# DC_Buck_Converter_5V_-_After.net
KiCad netlist of a schematic drawn in Altium Designer
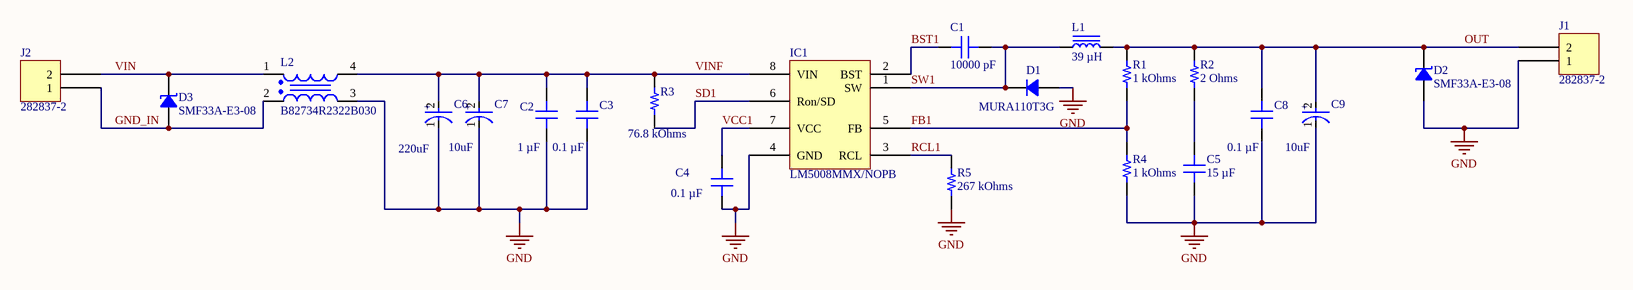
[diagram p0: DC_Buck_Converter_5V - After.SchDoc]

(export (version "E")
  (design (tool "Eeschema 10.0.6"))
  (components
    (comp (ref "C1")
      (value "10000 pF")
      (footprint "CAP 0603_1608")
      (description "CAP CER 10000PF 100V X7R 0603")
      (fields (field (name "PART NUMBER") "AC0603KRX7R0BB103") (field (name "MANUFACTURER") "Yageo"))
      (libsource (lib "Celestial Altium Library - altium_library") (part "Capacitor"))
    )
    (comp (ref "C2")
      (value "1 µF")
      (footprint "CAP 0603_1608")
      (description "CAP CER 1UF 50V X5R 0603")
      (fields (field (name "PART NUMBER") "UMK107ABJ105MAHT") (field (name "MANUFACTURER") "Taiyo Yuden"))
      (libsource (lib "Celestial Altium Library - altium_library") (part "Capacitor"))
    )
    (comp (ref "C3")
      (value "0.1 µF")
      (footprint "CAP 0603_1608")
      (description "CAP CER 0.1UF 50V X7R 0603")
      (fields (field (name "PART NUMBER") "C0603C104K5RAC7411") (field (name "MANUFACTURER") "KEMET"))
      (libsource (lib "Celestial Altium Library - altium_library") (part "Capacitor"))
    )
    (comp (ref "C4")
      (value "0.1 µF")
      (footprint "CAP 0603_1608")
      (description "CAP CER 0.1UF 50V X7R 0603")
      (fields (field (name "PART NUMBER") "C0603C104K5RAC7411") (field (name "MANUFACTURER") "KEMET"))
      (libsource (lib "Celestial Altium Library - altium_library") (part "Capacitor"))
    )
    (comp (ref "C5")
      (value "15 µF")
      (footprint "CAP 0603_1608")
      (description "CAP CER 15UF 6.3V X5R 0603")
      (fields
        (field (name "PART NUMBER") "C1608X5R0J156M080AC")
        (field (name "MANUFACTURER") "TDK Corporation")
      )
      (libsource (lib "Celestial Altium Library - altium_library") (part "Capacitor"))
    )
    (comp (ref "C6")
      (value "EEE-FC1H221P")
      (footprint "FP-FC-G-MFG")
      (description "CAP ALUM 220UF 20% 50V SMD")
      (fields
        (field (name "VOLTAGE") "50V")
        (field (name "TOLERANCE") "20%")
        (field (name "CAPACITANCE") "220uF")
      )
      (libsource (lib "Altium Content Vault") (part "203bc49f2ac43e59fd269a8c329ed05"))
    )
    (comp (ref "C7")
      (value "UUT1H100MCL1GS")
      (footprint "FP-UUT1H100MCL1GS-MFG")
      (description "CAP ALUM 10UF 20% 50V SMD")
      (fields
        (field (name "CAPACITANCE") "10uF")
        (field (name "VOLTAGE") "50V")
        (field (name "TOLERANCE") "20%")
      )
      (libsource (lib "Altium Content Vault") (part "cf48714ba7e38822c1575c7ec0b6d1f"))
    )
    (comp (ref "C8")
      (value "0.1 µF")
      (footprint "CAP 0603_1608")
      (description "CAP CER 0.1UF 50V X7R 0603")
      (fields (field (name "PART NUMBER") "C0603C104K5RAC7411") (field (name "MANUFACTURER") "KEMET"))
      (libsource (lib "Celestial Altium Library - altium_library") (part "Capacitor"))
    )
    (comp (ref "C9")
      (value "UUT1H100MCL1GS")
      (footprint "FP-UUT1H100MCL1GS-MFG")
      (description "CAP ALUM 10UF 20% 50V SMD")
      (fields
        (field (name "CAPACITANCE") "10uF")
        (field (name "VOLTAGE") "50V")
        (field (name "TOLERANCE") "20%")
      )
      (libsource (lib "Altium Content Vault") (part "cf48714ba7e38822c1575c7ec0b6d1f"))
    )
    (comp (ref "D1")
      (value "MURA110T3G")
      (footprint "DO214AC SMA")
      (description "DIODE GEN PURP 100V 2A SMA")
      (fields (field (name "MANUFACTURER") "ON Semiconductor"))
      (libsource (lib "Celestial Altium Library - altium_library") (part "Diode"))
    )
    (comp (ref "D2")
      (value "SMF33A-E3-08")
      (footprint "SMF DO-219AB")
      (description "TVS DIODE 33V 53.3V SMF")
      (fields (field (name "MANUFACTURER") "Vishay Semiconductor Diodes Division"))
      (libsource (lib "Celestial Altium Library - altium_library") (part "DIODE TVS UNI"))
    )
    (comp (ref "D3")
      (value "SMF33A-E3-08")
      (footprint "SMF DO-219AB")
      (description "TVS DIODE 33V 53.3V SMF")
      (fields (field (name "MANUFACTURER") "Vishay Semiconductor Diodes Division"))
      (libsource (lib "Celestial Altium Library - altium_library") (part "DIODE TVS UNI"))
    )
    (comp (ref "IC1")
      (value "LM5008MMX/NOPB")
      (footprint "TI VSSOP-8 DGK")
      (description "IC REG BUCK ADJ 350MA 8VSSOP")
      (fields (field (name "MANUFACTURER") "Texas Instruments"))
      (libsource (lib "Celestial Altium Library - altium_library") (part "TI LM5008"))
    )
    (comp (ref "J1")
      (value "282837-2")
      (footprint "TE 282837-2")
      (description "TERM BLK 2P SIDE ENT 5.08MM PCB")
      (fields (field (name "MANUFACTURER") "TE Connectivity AMP Connectors") (field (name "VOLTAGE") "300 V"))
      (libsource (lib "DC_Buck_Converter_5V") (part "282837-2"))
    )
    (comp (ref "J2")
      (value "282837-2")
      (footprint "TE 282837-2")
      (description "TERM BLK 2P SIDE ENT 5.08MM PCB")
      (fields (field (name "MANUFACTURER") "TE Connectivity AMP Connectors") (field (name "VOLTAGE") "300 V"))
      (libsource (lib "") (part "282837-2_1"))
    )
    (comp (ref "L1")
      (value "39 µH")
      (footprint "BOURNS SRR1280")
      (description "FIXED IND 39UH 3.2A 70 MOHM SMD")
      (fields (field (name "PART NUMBER") "SRR1280-390M") (field (name "MANUFACTURER") "Bourns Inc."))
      (libsource (lib "Celestial Altium Library - altium_library") (part "Inductor"))
    )
    (comp (ref "L2")
      (value "Choke Alt")
      (footprint "B82732R2112B30")
      (fields (field (name "PART NUMBER") "B82734R2322B030") (field (name "MANUFACTURER") "TDK"))
      (libsource (lib "Passives_Inductor_THT") (part "Choke Alt"))
    )
    (comp (ref "R1")
      (value "1 kOhms")
      (footprint "RES 0603_1608")
      (description "RES SMD 1K OHM 0.5% 1/10W 0603")
      (fields (field (name "PART NUMBER") "AT0603DRD071KL") (field (name "MANUFACTURER") "Yageo"))
      (libsource (lib "Celestial Altium Library - altium_library") (part "Resistor"))
    )
    (comp (ref "R2")
      (value "2 Ohms")
      (footprint "RES 0603_1608")
      (description "SULFUR TOLERANT CHIP RESISTORS")
      (fields (field (name "PART NUMBER") "SFR03EZPJ2R0") (field (name "MANUFACTURER") "Rohm Semiconductor"))
      (libsource (lib "Celestial Altium Library - altium_library") (part "Resistor"))
    )
    (comp (ref "R3")
      (value "76.8 kOhms")
      (footprint "RES 0603_1608")
      (description "RES SMD 76.8KOHM 0.1% 1/10W 0603")
      (fields (field (name "PART NUMBER") "RG1608P-7682-B-T5") (field (name "MANUFACTURER") "Susumu"))
      (libsource (lib "Celestial Altium Library - altium_library") (part "Resistor"))
    )
    (comp (ref "R4")
      (value "1 kOhms")
      (footprint "RES 0603_1608")
      (description "RES SMD 1K OHM 0.5% 1/10W 0603")
      (fields (field (name "PART NUMBER") "AT0603DRD071KL") (field (name "MANUFACTURER") "Yageo"))
      (libsource (lib "Celestial Altium Library - altium_library") (part "Resistor"))
    )
    (comp (ref "R5")
      (value "267 kOhms")
      (footprint "RES 0603_1608")
      (description "RES SMD 267K OHM 0.1% 1/10W 0603")
      (fields (field (name "PART NUMBER") "RT0603BRD07267KL") (field (name "MANUFACTURER") "Yageo"))
      (libsource (lib "Celestial Altium Library - altium_library") (part "Resistor"))
    )
  )
  (nets
    (net (code "1") (name "/BST1") (class "Default")
      (node (ref "C1") (pin "1") (pinfunction "1_1") (pintype "passive"))
      (node (ref "IC1") (pin "2") (pinfunction "BST_2") (pintype "passive"))
    )
    (net (code "2") (name "/FB1") (class "Default")
      (node (ref "IC1") (pin "5") (pinfunction "FB_5") (pintype "passive"))
      (node (ref "R1") (pin "1") (pinfunction "1_1") (pintype "passive"))
      (node (ref "R4") (pin "2") (pinfunction "2_2") (pintype "passive"))
    )
    (net (code "3") (name "/GND_IN") (class "Default")
      (node (ref "D3") (pin "1") (pinfunction "1_1") (pintype "passive"))
      (node (ref "J2") (pin "1") (pinfunction "1_1") (pintype "passive"))
      (node (ref "L2") (pin "2") (pinfunction "2_2") (pintype "passive"))
    )
    (net (code "4") (name "/OUT") (class "Default")
      (node (ref "C8") (pin "2") (pinfunction "2_2") (pintype "passive"))
      (node (ref "C9") (pin "2") (pinfunction "A_2") (pintype "passive"))
      (node (ref "D2") (pin "2") (pinfunction "2_2") (pintype "passive"))
      (node (ref "J1") (pin "2") (pinfunction "2_2") (pintype "passive"))
      (node (ref "L1") (pin "2") (pinfunction "2_2") (pintype "passive"))
      (node (ref "R1") (pin "2") (pinfunction "2_2") (pintype "passive"))
      (node (ref "R2") (pin "2") (pinfunction "2_2") (pintype "passive"))
    )
    (net (code "5") (name "/RCL1") (class "Default")
      (node (ref "IC1") (pin "3") (pinfunction "RCL_3") (pintype "passive"))
      (node (ref "R5") (pin "2") (pinfunction "2_2") (pintype "passive"))
    )
    (net (code "6") (name "/SD1") (class "Default")
      (node (ref "IC1") (pin "6") (pinfunction "Ron/SD_6") (pintype "passive"))
      (node (ref "R3") (pin "1") (pinfunction "1_1") (pintype "passive"))
    )
    (net (code "7") (name "/SW1") (class "Default")
      (node (ref "C1") (pin "2") (pinfunction "2_2") (pintype "passive"))
      (node (ref "D1") (pin "2") (pinfunction "2_2") (pintype "passive"))
      (node (ref "IC1") (pin "1") (pinfunction "SW_1") (pintype "passive"))
      (node (ref "L1") (pin "1") (pinfunction "1_1") (pintype "passive"))
    )
    (net (code "8") (name "/VCC1") (class "Default")
      (node (ref "C4") (pin "1") (pinfunction "1_1") (pintype "passive"))
      (node (ref "IC1") (pin "7") (pinfunction "VCC_7") (pintype "passive"))
    )
    (net (code "9") (name "/VIN") (class "Default")
      (node (ref "D3") (pin "2") (pinfunction "2_2") (pintype "passive"))
      (node (ref "J2") (pin "2") (pinfunction "2_2") (pintype "passive"))
      (node (ref "L2") (pin "1") (pinfunction "1_1") (pintype "passive"))
    )
    (net (code "10") (name "/VINF") (class "Default")
      (node (ref "C2") (pin "2") (pinfunction "2_2") (pintype "passive"))
      (node (ref "C3") (pin "2") (pinfunction "2_2") (pintype "passive"))
      (node (ref "C6") (pin "2") (pinfunction "A_2") (pintype "passive"))
      (node (ref "C7") (pin "2") (pinfunction "A_2") (pintype "passive"))
      (node (ref "IC1") (pin "8") (pinfunction "VIN_8") (pintype "passive"))
      (node (ref "L2") (pin "4") (pinfunction "4_4") (pintype "passive"))
      (node (ref "R3") (pin "2") (pinfunction "2_2") (pintype "passive"))
    )
    (net (code "11") (name "GND") (class "Default")
      (node (ref "C2") (pin "1") (pinfunction "1_1") (pintype "passive"))
      (node (ref "C3") (pin "1") (pinfunction "1_1") (pintype "passive"))
      (node (ref "C4") (pin "2") (pinfunction "2_2") (pintype "passive"))
      (node (ref "C5") (pin "1") (pinfunction "1_1") (pintype "passive"))
      (node (ref "C6") (pin "1") (pinfunction "C_1") (pintype "passive"))
      (node (ref "C7") (pin "1") (pinfunction "C_1") (pintype "passive"))
      (node (ref "C8") (pin "1") (pinfunction "1_1") (pintype "passive"))
      (node (ref "C9") (pin "1") (pinfunction "C_1") (pintype "passive"))
      (node (ref "D1") (pin "1") (pinfunction "1_1") (pintype "passive"))
      (node (ref "D2") (pin "1") (pinfunction "1_1") (pintype "passive"))
      (node (ref "IC1") (pin "4") (pinfunction "GND_4") (pintype "passive"))
      (node (ref "J1") (pin "1") (pinfunction "1_1") (pintype "passive"))
      (node (ref "L2") (pin "3") (pinfunction "3_3") (pintype "passive"))
      (node (ref "R4") (pin "1") (pinfunction "1_1") (pintype "passive"))
      (node (ref "R5") (pin "1") (pinfunction "1_1") (pintype "passive"))
    )
    (net (code "12") (name "Net-(C5-Pad2)") (class "Default")
      (node (ref "C5") (pin "2") (pinfunction "2_2") (pintype "passive"))
      (node (ref "R2") (pin "1") (pinfunction "1_1") (pintype "passive"))
    )
  )
)
